# dash8_40cw.net
KiCad netlist of a schematic drawn in EAGLE
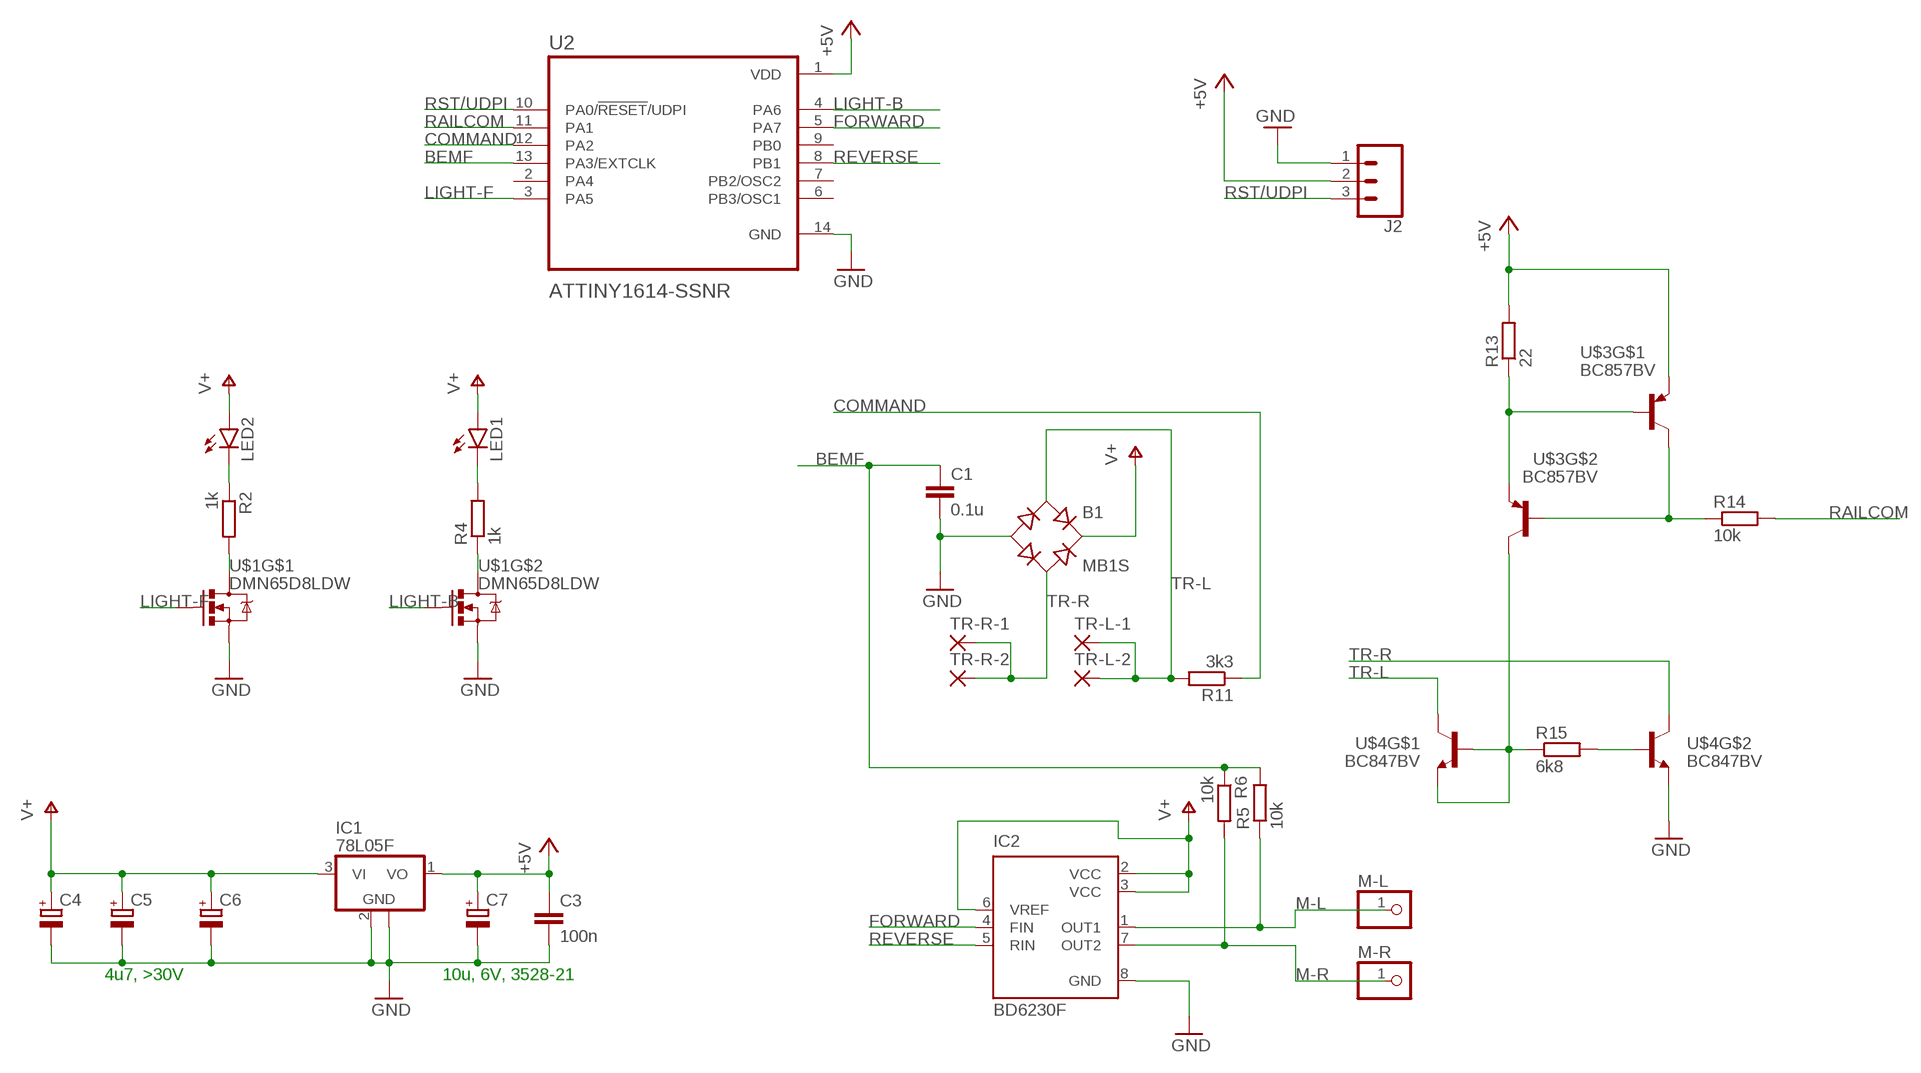
[diagram p0: schematic, sheet 1]

(export (version "E")
  (design (tool "Eeschema 10.0.6"))
  (components
    (comp (ref "B1")
      (value "MB1S")
      (footprint "eagle-import:SOIC-4")
      (libsource (lib "eagle-import") (part "MBS1"))
    )
    (comp (ref "C1")
      (value "0.1u")
      (footprint "eagle-import:C0805")
      (libsource (lib "eagle-import") (part "resistor_348_C-EUC0805"))
    )
    (comp (ref "C3")
      (value "100n")
      (footprint "eagle-import:C0805")
      (libsource (lib "eagle-import") (part "C-EUC0805"))
    )
    (comp (ref "C4")
      (value "CPOL-EUCT3528")
      (footprint "eagle-import:CT3528")
      (libsource (lib "eagle-import") (part "CPOL-EUCT3528"))
    )
    (comp (ref "C5")
      (value "CPOL-EUCT3528")
      (footprint "eagle-import:CT3528")
      (libsource (lib "eagle-import") (part "CPOL-EUCT3528"))
    )
    (comp (ref "C6")
      (value "CPOL-EUCT3528")
      (footprint "eagle-import:CT3528")
      (libsource (lib "eagle-import") (part "CPOL-EUCT3528"))
    )
    (comp (ref "C7")
      (value "CPOL-EUCT3528")
      (footprint "eagle-import:CT3528")
      (libsource (lib "eagle-import") (part "CPOL-EUCT3528"))
    )
    (comp (ref "IC1")
      (value "78L05F")
      (footprint "eagle-import:SOT89")
      (libsource (lib "eagle-import") (part "78LF05"))
    )
    (comp (ref "IC2")
      (value "BD6230F")
      (footprint "eagle-import:SOP8")
      (fields (field (name "MPN") "BD6230F-E2"))
      (libsource (lib "eagle-import") (part "BD623F0"))
    )
    (comp (ref "J2")
      (value "455-1750-1-ND")
      (footprint "eagle-import:1X03")
      (libsource (lib "eagle-import") (part "CONN_03"))
    )
    (comp (ref "LED1")
      (value "LED3MM")
      (footprint "eagle-import:LED3MM")
      (libsource (lib "eagle-import") (part "LED3MM"))
    )
    (comp (ref "LED2")
      (value "LED3MM")
      (footprint "eagle-import:LED3MM")
      (libsource (lib "eagle-import") (part "LED3MM"))
    )
    (comp (ref "M-L")
      (value "PINHD-1X1")
      (footprint "eagle-import:1X01")
      (libsource (lib "eagle-import") (part "PINHD-1X1"))
    )
    (comp (ref "M-R")
      (value "PINHD-1X1")
      (footprint "eagle-import:1X01")
      (libsource (lib "eagle-import") (part "PINHD-1X1"))
    )
    (comp (ref "R2")
      (value "1k")
      (footprint "eagle-import:R0603")
      (libsource (lib "eagle-import") (part "R-EU_R0603"))
    )
    (comp (ref "R4")
      (value "1k")
      (footprint "eagle-import:R0603")
      (libsource (lib "eagle-import") (part "R-EU_R0603"))
    )
    (comp (ref "R5")
      (value "10k")
      (footprint "eagle-import:R0603")
      (libsource (lib "eagle-import") (part "R-EU_R0603"))
    )
    (comp (ref "R6")
      (value "10k")
      (footprint "eagle-import:R0603")
      (libsource (lib "eagle-import") (part "R-EU_R0603"))
    )
    (comp (ref "R11")
      (value "3k3")
      (footprint "eagle-import:R0603")
      (libsource (lib "eagle-import") (part "R-EU_R0603"))
    )
    (comp (ref "R13")
      (value "22")
      (footprint "eagle-import:R0805")
      (libsource (lib "eagle-import") (part "R-EU_R0805"))
    )
    (comp (ref "R14")
      (value "10k")
      (footprint "eagle-import:R0805")
      (libsource (lib "eagle-import") (part "R-EU_R0805"))
    )
    (comp (ref "R15")
      (value "6k8")
      (footprint "eagle-import:R0805")
      (libsource (lib "eagle-import") (part "R-EU_R0805"))
    )
    (comp (ref "TR-L-1")
      (value "SMD5")
      (footprint "eagle-import:SMD2,54-5,08")
      (libsource (lib "eagle-import") (part "SMD5"))
    )
    (comp (ref "TR-L-2")
      (value "SMD5")
      (footprint "eagle-import:SMD2,54-5,08")
      (libsource (lib "eagle-import") (part "SMD5"))
    )
    (comp (ref "TR-R-1")
      (value "SMD5")
      (footprint "eagle-import:SMD2,54-5,08")
      (libsource (lib "eagle-import") (part "SMD5"))
    )
    (comp (ref "TR-R-2")
      (value "SMD5")
      (footprint "eagle-import:SMD2,54-5,08")
      (libsource (lib "eagle-import") (part "SMD5"))
    )
    (comp (ref "U$1")
      (value "DMN65D8LDW")
      (footprint "eagle-import:SOT363")
      (libsource (lib "eagle-import") (part "DMN65D8LDW"))
    )
    (comp (ref "U$3")
      (value "BC857BV")
      (footprint "eagle-import:SOT-666")
      (libsource (lib "eagle-import") (part "BC857BV"))
    )
    (comp (ref "U$4")
      (value "BC847BV")
      (footprint "eagle-import:SOT-666")
      (libsource (lib "eagle-import") (part "BC847BV"))
    )
    (comp (ref "U2")
      (value "ATTINY1614-SSNR")
      (footprint "eagle-import:SOIC127P600X175-14N")
      (fields (field (name "MF") "Microchip"))
      (libsource (lib "eagle-import") (part "ATTINY1614-SSNR"))
    )
  )
  (nets
    (net (code "1") (name "+5V") (class "Default")
      (node (ref "C3") (pin "1") (pinfunction "1_1") (pintype "passive"))
      (node (ref "C7") (pin "+") (pinfunction "+_+") (pintype "passive"))
      (node (ref "IC1") (pin "1") (pinfunction "VO_1") (pintype "passive"))
      (node (ref "J2") (pin "2") (pinfunction "2_2") (pintype "passive"))
      (node (ref "R13") (pin "2") (pinfunction "2_2") (pintype "passive"))
      (node (ref "U$3") (pin "P$1") (pinfunction "E_P$1") (pintype "passive"))
      (node (ref "U2") (pin "1") (pinfunction "VDD_1") (pintype "power_in"))
    )
    (net (code "2") (name "/BEMF") (class "Default")
      (node (ref "C1") (pin "1") (pinfunction "1_1") (pintype "passive"))
      (node (ref "R5") (pin "2") (pinfunction "2_2") (pintype "passive"))
      (node (ref "R6") (pin "1") (pinfunction "1_1") (pintype "passive"))
      (node (ref "U2") (pin "13") (pinfunction "PA3/EXTCLK_13") (pintype "bidirectional"))
    )
    (net (code "3") (name "/COMMAND") (class "Default")
      (node (ref "R11") (pin "1") (pinfunction "1_1") (pintype "passive"))
      (node (ref "U2") (pin "12") (pinfunction "PA2_12") (pintype "bidirectional"))
    )
    (net (code "4") (name "/FORWARD") (class "Default")
      (node (ref "IC2") (pin "4") (pinfunction "FIN_4") (pintype "input"))
      (node (ref "U2") (pin "5") (pinfunction "PA7_5") (pintype "bidirectional"))
    )
    (net (code "5") (name "/LIGHT-B") (class "Default")
      (node (ref "U$1") (pin "P$5") (pinfunction "G_P$5") (pintype "passive"))
      (node (ref "U2") (pin "4") (pinfunction "PA6_4") (pintype "bidirectional"))
    )
    (net (code "6") (name "/LIGHT-F") (class "Default")
      (node (ref "U$1") (pin "P$2") (pinfunction "G_P$2") (pintype "passive"))
      (node (ref "U2") (pin "3") (pinfunction "PA5_3") (pintype "bidirectional"))
    )
    (net (code "7") (name "/M-L") (class "Default")
      (node (ref "IC2") (pin "1") (pinfunction "OUT1_1") (pintype "output"))
      (node (ref "M-L") (pin "1") (pinfunction "1_1") (pintype "passive"))
      (node (ref "R5") (pin "1") (pinfunction "1_1") (pintype "passive"))
    )
    (net (code "8") (name "/M-R") (class "Default")
      (node (ref "IC2") (pin "7") (pinfunction "OUT2_7") (pintype "output"))
      (node (ref "M-R") (pin "1") (pinfunction "1_1") (pintype "passive"))
      (node (ref "R6") (pin "2") (pinfunction "2_2") (pintype "passive"))
    )
    (net (code "9") (name "/RAILCOM") (class "Default")
      (node (ref "R14") (pin "2") (pinfunction "2_2") (pintype "passive"))
      (node (ref "U2") (pin "11") (pinfunction "PA1_11") (pintype "bidirectional"))
    )
    (net (code "10") (name "/REVERSE") (class "Default")
      (node (ref "IC2") (pin "5") (pinfunction "RIN_5") (pintype "input"))
      (node (ref "U2") (pin "8") (pinfunction "PB1_8") (pintype "bidirectional"))
    )
    (net (code "11") (name "/RST{slash}UDPI") (class "Default")
      (node (ref "J2") (pin "3") (pinfunction "3_3") (pintype "passive"))
      (node (ref "U2") (pin "10") (pinfunction "PA0/~{RESET}/UDPI_10") (pintype "bidirectional"))
    )
    (net (code "12") (name "/TR-L") (class "Default")
      (node (ref "B1") (pin "~1") (pinfunction "AC1_~1") (pintype "passive"))
      (node (ref "R11") (pin "2") (pinfunction "2_2") (pintype "passive"))
      (node (ref "TR-L-1") (pin "1") (pinfunction "P_1") (pintype "passive"))
      (node (ref "TR-L-2") (pin "1") (pinfunction "P_1") (pintype "passive"))
      (node (ref "U$4") (pin "P$6") (pinfunction "C_P$6") (pintype "passive"))
    )
    (net (code "13") (name "/TR-R") (class "Default")
      (node (ref "B1") (pin "~2") (pinfunction "AC2_~2") (pintype "passive"))
      (node (ref "TR-R-1") (pin "1") (pinfunction "P_1") (pintype "passive"))
      (node (ref "TR-R-2") (pin "1") (pinfunction "P_1") (pintype "passive"))
      (node (ref "U$4") (pin "P$3") (pinfunction "C_P$3") (pintype "passive"))
    )
    (net (code "14") (name "GND") (class "Default")
      (node (ref "B1") (pin "-") (pinfunction "-_-") (pintype "passive"))
      (node (ref "C1") (pin "2") (pinfunction "2_2") (pintype "passive"))
      (node (ref "C3") (pin "2") (pinfunction "2_2") (pintype "passive"))
      (node (ref "C4") (pin "-") (pinfunction "-_-") (pintype "passive"))
      (node (ref "C5") (pin "-") (pinfunction "-_-") (pintype "passive"))
      (node (ref "C6") (pin "-") (pinfunction "-_-") (pintype "passive"))
      (node (ref "C7") (pin "-") (pinfunction "-_-") (pintype "passive"))
      (node (ref "IC1") (pin "2") (pinfunction "GND_2") (pintype "passive"))
      (node (ref "IC1") (pin "2@1") (pinfunction "GND_2@1") (pintype "passive"))
      (node (ref "IC2") (pin "8") (pinfunction "GND_8") (pintype "power_in"))
      (node (ref "J2") (pin "1") (pinfunction "1_1") (pintype "passive"))
      (node (ref "U$1") (pin "P$3") (pinfunction "S_P$3") (pintype "passive"))
      (node (ref "U$1") (pin "P$6") (pinfunction "S_P$6") (pintype "passive"))
      (node (ref "U$4") (pin "P$4") (pinfunction "E_P$4") (pintype "passive"))
      (node (ref "U2") (pin "14") (pinfunction "GND_14") (pintype "power_in"))
    )
    (net (code "15") (name "Net-(LED1-C)") (class "Default")
      (node (ref "LED1") (pin "K") (pinfunction "C_K") (pintype "passive"))
      (node (ref "R4") (pin "2") (pinfunction "2_2") (pintype "passive"))
    )
    (net (code "16") (name "Net-(LED2-C)") (class "Default")
      (node (ref "LED2") (pin "K") (pinfunction "C_K") (pintype "passive"))
      (node (ref "R2") (pin "1") (pinfunction "1_1") (pintype "passive"))
    )
    (net (code "17") (name "Net-(U$1A-D)") (class "Default")
      (node (ref "R2") (pin "2") (pinfunction "2_2") (pintype "passive"))
      (node (ref "U$1") (pin "P$4") (pinfunction "D_P$4") (pintype "passive"))
    )
    (net (code "18") (name "Net-(U$1B-D)") (class "Default")
      (node (ref "R4") (pin "1") (pinfunction "1_1") (pintype "passive"))
      (node (ref "U$1") (pin "P$1") (pinfunction "D_P$1") (pintype "passive"))
    )
    (net (code "19") (name "Net-(U$3A-B)") (class "Default")
      (node (ref "R13") (pin "1") (pinfunction "1_1") (pintype "passive"))
      (node (ref "U$3") (pin "P$2") (pinfunction "B_P$2") (pintype "passive"))
      (node (ref "U$3") (pin "P$4") (pinfunction "E_P$4") (pintype "passive"))
    )
    (net (code "20") (name "Net-(U$3A-C)") (class "Default")
      (node (ref "R14") (pin "1") (pinfunction "1_1") (pintype "passive"))
      (node (ref "U$3") (pin "P$5") (pinfunction "B_P$5") (pintype "passive"))
      (node (ref "U$3") (pin "P$6") (pinfunction "C_P$6") (pintype "passive"))
    )
    (net (code "21") (name "Net-(U$3B-C)") (class "Default")
      (node (ref "R15") (pin "1") (pinfunction "1_1") (pintype "passive"))
      (node (ref "U$3") (pin "P$3") (pinfunction "C_P$3") (pintype "passive"))
      (node (ref "U$4") (pin "P$1") (pinfunction "E_P$1") (pintype "passive"))
      (node (ref "U$4") (pin "P$2") (pinfunction "B_P$2") (pintype "passive"))
    )
    (net (code "22") (name "Net-(U$4B-B)") (class "Default")
      (node (ref "R15") (pin "2") (pinfunction "2_2") (pintype "passive"))
      (node (ref "U$4") (pin "P$5") (pinfunction "B_P$5") (pintype "passive"))
    )
    (net (code "23") (name "V+") (class "Default")
      (node (ref "B1") (pin "+") (pinfunction "+_+") (pintype "passive"))
      (node (ref "C4") (pin "+") (pinfunction "+_+") (pintype "passive"))
      (node (ref "C5") (pin "+") (pinfunction "+_+") (pintype "passive"))
      (node (ref "C6") (pin "+") (pinfunction "+_+") (pintype "passive"))
      (node (ref "IC1") (pin "3") (pinfunction "VI_3") (pintype "input"))
      (node (ref "IC2") (pin "2") (pinfunction "VCC_2") (pintype "power_in"))
      (node (ref "IC2") (pin "3") (pinfunction "VCC_3") (pintype "power_in"))
      (node (ref "IC2") (pin "6") (pinfunction "VREF_6") (pintype "passive"))
      (node (ref "LED1") (pin "A") (pinfunction "A_A") (pintype "passive"))
      (node (ref "LED2") (pin "A") (pinfunction "A_A") (pintype "passive"))
    )
    (net (code "24") (name "unconnected-(U2-PA4-Pad2)") (class "Default")
      (node (ref "U2") (pin "2") (pinfunction "PA4_2") (pintype "bidirectional"))
    )
    (net (code "25") (name "unconnected-(U2-PB0-Pad9)") (class "Default")
      (node (ref "U2") (pin "9") (pinfunction "PB0_9") (pintype "bidirectional"))
    )
    (net (code "26") (name "unconnected-(U2-PB2{slash}OSC2-Pad7)") (class "Default")
      (node (ref "U2") (pin "7") (pinfunction "PB2/OSC2_7") (pintype "bidirectional"))
    )
    (net (code "27") (name "unconnected-(U2-PB3{slash}OSC1-Pad6)") (class "Default")
      (node (ref "U2") (pin "6") (pinfunction "PB3/OSC1_6") (pintype "bidirectional"))
    )
  )
)
